# schema_v4_1_SMD_DIP.net
KiCad netlist of a schematic drawn in EAGLE
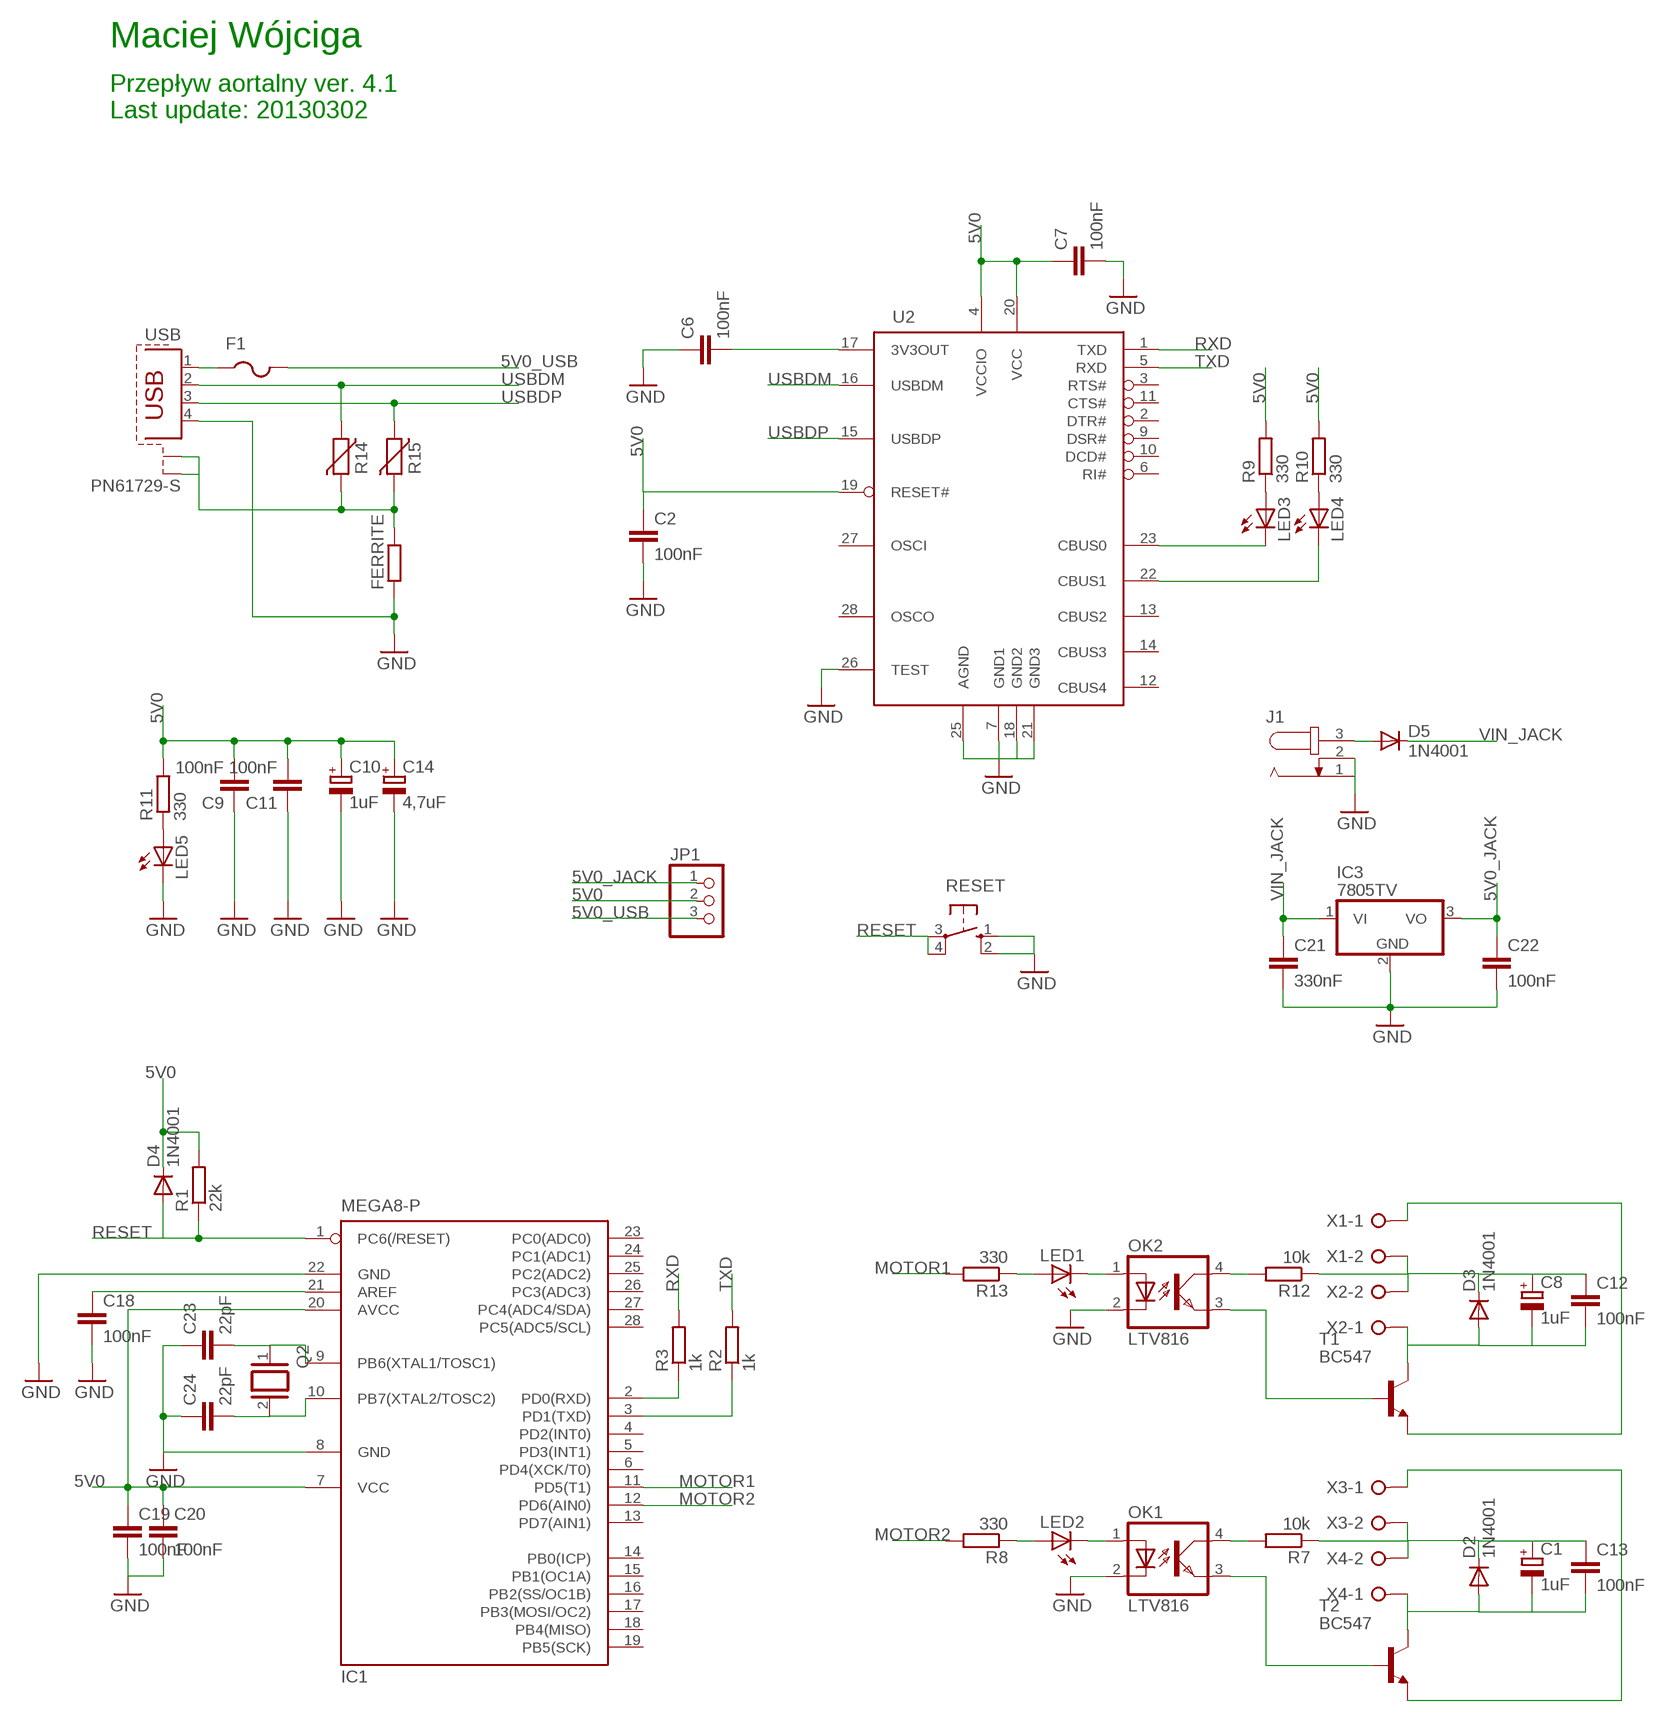
[diagram p0: schematic, sheet 1]

(export (version "E")
  (design (tool "Eeschema 10.0.6"))
  (components
    (comp (ref "C1")
      (value "1uF")
      (footprint "eagle-import:E2,5-5")
      (libsource (lib "eagle-import") (part "CPOL-EUE2.5-5"))
    )
    (comp (ref "C2")
      (value "100nF")
      (footprint "eagle-import:C0603K")
      (libsource (lib "eagle-import") (part "C-EUC0603K"))
    )
    (comp (ref "C6")
      (value "100nF")
      (footprint "eagle-import:C0603K")
      (libsource (lib "eagle-import") (part "C-EUC0603K"))
    )
    (comp (ref "C7")
      (value "100nF")
      (footprint "eagle-import:C0603K")
      (libsource (lib "eagle-import") (part "C-EUC0603K"))
    )
    (comp (ref "C8")
      (value "1uF")
      (footprint "eagle-import:E2,5-5")
      (libsource (lib "eagle-import") (part "CPOL-EUE2.5-5"))
    )
    (comp (ref "C9")
      (value "100nF")
      (footprint "eagle-import:C025-025X050")
      (libsource (lib "eagle-import") (part "C-EU025-025X050"))
    )
    (comp (ref "C10")
      (value "1uF")
      (footprint "eagle-import:E2,5-5")
      (libsource (lib "eagle-import") (part "CPOL-EUE2.5-5"))
    )
    (comp (ref "C11")
      (value "100nF")
      (footprint "eagle-import:C025-025X050")
      (libsource (lib "eagle-import") (part "C-EU025-025X050"))
    )
    (comp (ref "C12")
      (value "100nF")
      (footprint "eagle-import:C025-025X050")
      (libsource (lib "eagle-import") (part "C-EU025-025X050"))
    )
    (comp (ref "C13")
      (value "100nF")
      (footprint "eagle-import:C025-025X050")
      (libsource (lib "eagle-import") (part "C-EU025-025X050"))
    )
    (comp (ref "C14")
      (value "4,7uF")
      (footprint "eagle-import:E2,5-5")
      (libsource (lib "eagle-import") (part "CPOL-EUE2.5-5"))
    )
    (comp (ref "C18")
      (value "100nF")
      (footprint "eagle-import:C0805")
      (libsource (lib "eagle-import") (part "C-EUC0805"))
    )
    (comp (ref "C19")
      (value "100nF")
      (footprint "eagle-import:C025-025X050")
      (libsource (lib "eagle-import") (part "C-EU025-025X050"))
    )
    (comp (ref "C20")
      (value "100nF")
      (footprint "eagle-import:C025-025X050")
      (libsource (lib "eagle-import") (part "C-EU025-025X050"))
    )
    (comp (ref "C21")
      (value "330nF")
      (footprint "eagle-import:C025-025X050")
      (libsource (lib "eagle-import") (part "C-EU025-025X050"))
    )
    (comp (ref "C22")
      (value "100nF")
      (footprint "eagle-import:C025-025X050")
      (libsource (lib "eagle-import") (part "C-EU025-025X050"))
    )
    (comp (ref "C23")
      (value "22pF")
      (footprint "eagle-import:C025-025X050")
      (libsource (lib "eagle-import") (part "C-EU025-025X050"))
    )
    (comp (ref "C24")
      (value "22pF")
      (footprint "eagle-import:C025-025X050")
      (libsource (lib "eagle-import") (part "C-EU025-025X050"))
    )
    (comp (ref "D2")
      (value "1N4001")
      (footprint "eagle-import:DO41-10")
      (libsource (lib "eagle-import") (part "1N4004"))
    )
    (comp (ref "D3")
      (value "1N4001")
      (footprint "eagle-import:DO41-10")
      (libsource (lib "eagle-import") (part "1N4004"))
    )
    (comp (ref "D4")
      (value "1N4001")
      (footprint "eagle-import:DO41-10")
      (libsource (lib "eagle-import") (part "1N4004"))
    )
    (comp (ref "D5")
      (value "1N4001")
      (footprint "eagle-import:DO41-10")
      (libsource (lib "eagle-import") (part "1N4004"))
    )
    (comp (ref "F1")
      (value "PTCFUSE-1812")
      (footprint "eagle-import:1812")
      (libsource (lib "eagle-import") (part "PTCFUSE-1812"))
    )
    (comp (ref "FERRITE")
      (value "R-EU_M0805")
      (footprint "eagle-import:M0805")
      (libsource (lib "eagle-import") (part "resistor_R-EU_M0805"))
    )
    (comp (ref "IC1")
      (value "MEGA8-P")
      (footprint "eagle-import:DIL28-3")
      (libsource (lib "eagle-import") (part "MEGA8-P"))
    )
    (comp (ref "IC3")
      (value "7805TV")
      (footprint "eagle-import:TO220V")
      (libsource (lib "eagle-import") (part "78TV05"))
    )
    (comp (ref "J1")
      (value "JACK-PLUG0")
      (footprint "eagle-import:SPC4077")
      (libsource (lib "eagle-import") (part "JACK-PLUG0"))
    )
    (comp (ref "JP1")
      (value "PINHD-1X3")
      (footprint "eagle-import:1X03")
      (libsource (lib "eagle-import") (part "PINHD-1X3"))
    )
    (comp (ref "LED1")
      (value "LED3MM")
      (footprint "eagle-import:LED3MM")
      (libsource (lib "eagle-import") (part "LED3MM"))
    )
    (comp (ref "LED2")
      (value "LED3MM")
      (footprint "eagle-import:LED3MM")
      (libsource (lib "eagle-import") (part "LED3MM"))
    )
    (comp (ref "LED3")
      (value "LED3MM")
      (footprint "eagle-import:LED3MM")
      (libsource (lib "eagle-import") (part "LED3MM"))
    )
    (comp (ref "LED4")
      (value "LED3MM")
      (footprint "eagle-import:LED3MM")
      (libsource (lib "eagle-import") (part "LED3MM"))
    )
    (comp (ref "LED5")
      (value "LED3MM")
      (footprint "eagle-import:LED3MM")
      (libsource (lib "eagle-import") (part "LED3MM"))
    )
    (comp (ref "OK1")
      (value "LTV816")
      (footprint "eagle-import:DIL04")
      (libsource (lib "eagle-import") (part "LTV816"))
    )
    (comp (ref "OK2")
      (value "LTV816")
      (footprint "eagle-import:DIL04")
      (libsource (lib "eagle-import") (part "LTV816"))
    )
    (comp (ref "Q2")
      (value "XTAL/S")
      (footprint "eagle-import:QS")
      (libsource (lib "eagle-import") (part "XTAL/S"))
    )
    (comp (ref "R1")
      (value "22k")
      (footprint "eagle-import:0207_10")
      (libsource (lib "eagle-import") (part "R-EU_0207/10"))
    )
    (comp (ref "R2")
      (value "1k")
      (footprint "eagle-import:0207_10")
      (libsource (lib "eagle-import") (part "R-EU_0207/10"))
    )
    (comp (ref "R3")
      (value "1k")
      (footprint "eagle-import:0207_10")
      (libsource (lib "eagle-import") (part "R-EU_0207/10"))
    )
    (comp (ref "R7")
      (value "10k")
      (footprint "eagle-import:0207_10")
      (libsource (lib "eagle-import") (part "R-EU_0207/10"))
    )
    (comp (ref "R8")
      (value "330")
      (footprint "eagle-import:0207_10")
      (libsource (lib "eagle-import") (part "R-EU_0207/10"))
    )
    (comp (ref "R9")
      (value "330")
      (footprint "eagle-import:0207_10")
      (libsource (lib "eagle-import") (part "R-EU_0207/10"))
    )
    (comp (ref "R10")
      (value "330")
      (footprint "eagle-import:0207_10")
      (libsource (lib "eagle-import") (part "R-EU_0207/10"))
    )
    (comp (ref "R11")
      (value "330")
      (footprint "eagle-import:0207_10")
      (libsource (lib "eagle-import") (part "R-EU_0207/10"))
    )
    (comp (ref "R12")
      (value "10k")
      (footprint "eagle-import:0207_10")
      (libsource (lib "eagle-import") (part "R-EU_0207/10"))
    )
    (comp (ref "R13")
      (value "330")
      (footprint "eagle-import:0207_10")
      (libsource (lib "eagle-import") (part "R-EU_0207/10"))
    )
    (comp (ref "R14")
      (value "VARISTORCN0603")
      (footprint "eagle-import:CT_CN0603")
      (libsource (lib "eagle-import") (part "VARISTORCN0603"))
    )
    (comp (ref "R15")
      (value "VARISTORCN0603")
      (footprint "eagle-import:CT_CN0603")
      (libsource (lib "eagle-import") (part "VARISTORCN0603"))
    )
    (comp (ref "RESET")
      (value "10-XX")
      (footprint "eagle-import:B3F-10XX")
      (fields (field (name "MPN") "B3F-1000"))
      (libsource (lib "eagle-import") (part "10-XX"))
    )
    (comp (ref "T1")
      (value "BC547")
      (footprint "eagle-import:TO92")
      (libsource (lib "eagle-import") (part "BC547"))
    )
    (comp (ref "T2")
      (value "BC547")
      (footprint "eagle-import:TO92")
      (libsource (lib "eagle-import") (part "BC547"))
    )
    (comp (ref "U2")
      (value "FT232RL")
      (footprint "eagle-import:SSOP28DB")
      (libsource (lib "eagle-import") (part "FT232RL"))
    )
    (comp (ref "USB")
      (value "PN61729-S")
      (footprint "eagle-import:PN61729-S")
      (fields (field (name "OC_FARNELL") "unknown") (field (name "OC_NEWARK") "unknown"))
      (libsource (lib "eagle-import") (part "PN61729-S"))
    )
    (comp (ref "X1")
      (value "W237-02P")
      (footprint "eagle-import:W237-132")
      (fields (field (name "OC_FARNELL") "unknown") (field (name "OC_NEWARK") "unknown"))
      (libsource (lib "eagle-import") (part "W237-02P"))
    )
    (comp (ref "X2")
      (value "W237-02P")
      (footprint "eagle-import:W237-132")
      (fields (field (name "OC_FARNELL") "unknown") (field (name "OC_NEWARK") "unknown"))
      (libsource (lib "eagle-import") (part "W237-02P"))
    )
    (comp (ref "X3")
      (value "W237-02P")
      (footprint "eagle-import:W237-132")
      (fields (field (name "OC_FARNELL") "unknown") (field (name "OC_NEWARK") "unknown"))
      (libsource (lib "eagle-import") (part "W237-02P"))
    )
    (comp (ref "X4")
      (value "W237-02P")
      (footprint "eagle-import:W237-132")
      (fields (field (name "OC_FARNELL") "unknown") (field (name "OC_NEWARK") "unknown"))
      (libsource (lib "eagle-import") (part "W237-02P"))
    )
  )
  (nets
    (net (code "1") (name "/5V0") (class "Default")
      (node (ref "C10") (pin "+") (pinfunction "+_+") (pintype "passive"))
      (node (ref "C11") (pin "2") (pinfunction "2_2") (pintype "passive"))
      (node (ref "C14") (pin "+") (pinfunction "+_+") (pintype "passive"))
      (node (ref "C19") (pin "1") (pinfunction "1_1") (pintype "passive"))
      (node (ref "C2") (pin "1") (pinfunction "1_1") (pintype "passive"))
      (node (ref "C20") (pin "1") (pinfunction "1_1") (pintype "passive"))
      (node (ref "C7") (pin "1") (pinfunction "1_1") (pintype "passive"))
      (node (ref "C9") (pin "2") (pinfunction "2_2") (pintype "passive"))
      (node (ref "D4") (pin "C") (pinfunction "C_C") (pintype "passive"))
      (node (ref "IC1") (pin "20") (pinfunction "AVCC_20") (pintype "power_in"))
      (node (ref "IC1") (pin "7") (pinfunction "VCC_7") (pintype "power_in"))
      (node (ref "JP1") (pin "2") (pinfunction "2_2") (pintype "passive"))
      (node (ref "R1") (pin "2") (pinfunction "2_2") (pintype "passive"))
      (node (ref "R10") (pin "2") (pinfunction "2_2") (pintype "passive"))
      (node (ref "R11") (pin "2") (pinfunction "2_2") (pintype "passive"))
      (node (ref "R9") (pin "2") (pinfunction "2_2") (pintype "passive"))
      (node (ref "U2") (pin "19") (pinfunction "RESET#_19") (pintype "input"))
      (node (ref "U2") (pin "20") (pinfunction "VCC_20") (pintype "power_in"))
      (node (ref "U2") (pin "4") (pinfunction "VCCIO_4") (pintype "power_in"))
    )
    (net (code "2") (name "/5V0_JACK") (class "Default")
      (node (ref "C22") (pin "1") (pinfunction "1_1") (pintype "passive"))
      (node (ref "IC3") (pin "3") (pinfunction "VO_3") (pintype "passive"))
      (node (ref "JP1") (pin "1") (pinfunction "1_1") (pintype "passive"))
    )
    (net (code "3") (name "/5V0_USB") (class "Default")
      (node (ref "F1") (pin "2") (pinfunction "2_2") (pintype "passive"))
      (node (ref "JP1") (pin "3") (pinfunction "3_3") (pintype "passive"))
    )
    (net (code "4") (name "/MOTOR1") (class "Default")
      (node (ref "IC1") (pin "11") (pinfunction "PD5(T1)_11") (pintype "bidirectional"))
      (node (ref "R13") (pin "2") (pinfunction "2_2") (pintype "passive"))
    )
    (net (code "5") (name "/MOTOR2") (class "Default")
      (node (ref "IC1") (pin "12") (pinfunction "PD6(AIN0)_12") (pintype "bidirectional"))
      (node (ref "R8") (pin "2") (pinfunction "2_2") (pintype "passive"))
    )
    (net (code "6") (name "/RESET") (class "Default")
      (node (ref "D4") (pin "A") (pinfunction "A_A") (pintype "passive"))
      (node (ref "IC1") (pin "1") (pinfunction "PC6(/RESET)_1") (pintype "bidirectional"))
      (node (ref "R1") (pin "1") (pinfunction "1_1") (pintype "passive"))
      (node (ref "RESET") (pin "3") (pinfunction "P_3") (pintype "passive"))
      (node (ref "RESET") (pin "4") (pinfunction "P1_4") (pintype "passive"))
    )
    (net (code "7") (name "/RXD") (class "Default")
      (node (ref "R3") (pin "2") (pinfunction "2_2") (pintype "passive"))
      (node (ref "U2") (pin "1") (pinfunction "TXD_1") (pintype "output"))
    )
    (net (code "8") (name "/TXD") (class "Default")
      (node (ref "R2") (pin "2") (pinfunction "2_2") (pintype "passive"))
      (node (ref "U2") (pin "5") (pinfunction "RXD_5") (pintype "input"))
    )
    (net (code "9") (name "/USBDM") (class "Default")
      (node (ref "R14") (pin "1") (pinfunction "1_1") (pintype "passive"))
      (node (ref "U2") (pin "16") (pinfunction "USBDM_16") (pintype "bidirectional"))
      (node (ref "USB") (pin "2") (pinfunction "2_2") (pintype "passive"))
    )
    (net (code "10") (name "/USBDP") (class "Default")
      (node (ref "R15") (pin "1") (pinfunction "1_1") (pintype "passive"))
      (node (ref "U2") (pin "15") (pinfunction "USBDP_15") (pintype "bidirectional"))
      (node (ref "USB") (pin "3") (pinfunction "3_3") (pintype "passive"))
    )
    (net (code "11") (name "/VIN_JACK") (class "Default")
      (node (ref "C21") (pin "1") (pinfunction "1_1") (pintype "passive"))
      (node (ref "D5") (pin "C") (pinfunction "C_C") (pintype "passive"))
      (node (ref "IC3") (pin "1") (pinfunction "VI_1") (pintype "input"))
    )
    (net (code "12") (name "GND") (class "Default")
      (node (ref "C10") (pin "-") (pinfunction "-_-") (pintype "passive"))
      (node (ref "C11") (pin "1") (pinfunction "1_1") (pintype "passive"))
      (node (ref "C14") (pin "-") (pinfunction "-_-") (pintype "passive"))
      (node (ref "C18") (pin "2") (pinfunction "2_2") (pintype "passive"))
      (node (ref "C19") (pin "2") (pinfunction "2_2") (pintype "passive"))
      (node (ref "C2") (pin "2") (pinfunction "2_2") (pintype "passive"))
      (node (ref "C20") (pin "2") (pinfunction "2_2") (pintype "passive"))
      (node (ref "C21") (pin "2") (pinfunction "2_2") (pintype "passive"))
      (node (ref "C22") (pin "2") (pinfunction "2_2") (pintype "passive"))
      (node (ref "C23") (pin "1") (pinfunction "1_1") (pintype "passive"))
      (node (ref "C24") (pin "1") (pinfunction "1_1") (pintype "passive"))
      (node (ref "C6") (pin "1") (pinfunction "1_1") (pintype "passive"))
      (node (ref "C7") (pin "2") (pinfunction "2_2") (pintype "passive"))
      (node (ref "C9") (pin "1") (pinfunction "1_1") (pintype "passive"))
      (node (ref "FERRITE") (pin "1") (pinfunction "1_1") (pintype "passive"))
      (node (ref "IC1") (pin "22") (pinfunction "GND_22") (pintype "power_in"))
      (node (ref "IC1") (pin "8") (pinfunction "GND_8") (pintype "power_in"))
      (node (ref "IC3") (pin "2") (pinfunction "GND_2") (pintype "passive"))
      (node (ref "J1") (pin "1") (pinfunction "1_1") (pintype "passive"))
      (node (ref "J1") (pin "2") (pinfunction "2_2") (pintype "passive"))
      (node (ref "LED5") (pin "K") (pinfunction "C_K") (pintype "passive"))
      (node (ref "OK1") (pin "2") (pinfunction "C_2") (pintype "passive"))
      (node (ref "OK2") (pin "2") (pinfunction "C_2") (pintype "passive"))
      (node (ref "RESET") (pin "1") (pinfunction "S_1") (pintype "passive"))
      (node (ref "RESET") (pin "2") (pinfunction "S1_2") (pintype "passive"))
      (node (ref "U2") (pin "18") (pinfunction "GND2_18") (pintype "power_in"))
      (node (ref "U2") (pin "21") (pinfunction "GND3_21") (pintype "power_in"))
      (node (ref "U2") (pin "25") (pinfunction "AGND_25") (pintype "power_in"))
      (node (ref "U2") (pin "26") (pinfunction "TEST_26") (pintype "input"))
      (node (ref "U2") (pin "7") (pinfunction "GND1_7") (pintype "power_in"))
      (node (ref "USB") (pin "4") (pinfunction "4_4") (pintype "passive"))
    )
    (net (code "13") (name "Net-(D5-PadA)") (class "Default")
      (node (ref "D5") (pin "A") (pinfunction "A_A") (pintype "passive"))
      (node (ref "J1") (pin "3") (pinfunction "3_3") (pintype "passive"))
    )
    (net (code "14") (name "Net-(F1-Pad1)") (class "Default")
      (node (ref "F1") (pin "1") (pinfunction "1_1") (pintype "passive"))
      (node (ref "USB") (pin "1") (pinfunction "1_1") (pintype "passive"))
    )
    (net (code "15") (name "Net-(FERRITE-Pad2)") (class "Default")
      (node (ref "FERRITE") (pin "2") (pinfunction "2_2") (pintype "passive"))
      (node (ref "R14") (pin "2") (pinfunction "2_2") (pintype "passive"))
      (node (ref "R15") (pin "2") (pinfunction "2_2") (pintype "passive"))
      (node (ref "USB") (pin "S1") (pinfunction "S1_S1") (pintype "passive"))
      (node (ref "USB") (pin "S2") (pinfunction "S2_S2") (pintype "passive"))
    )
    (net (code "16") (name "Net-(IC1-AREF)") (class "Default")
      (node (ref "C18") (pin "1") (pinfunction "1_1") (pintype "passive"))
      (node (ref "IC1") (pin "21") (pinfunction "AREF_21") (pintype "passive"))
    )
    (net (code "17") (name "Net-(IC1-PB6(XTAL1{slash}TOSC1))") (class "Default")
      (node (ref "C23") (pin "2") (pinfunction "2_2") (pintype "passive"))
      (node (ref "IC1") (pin "9") (pinfunction "PB6(XTAL1/TOSC1)_9") (pintype "bidirectional"))
      (node (ref "Q2") (pin "1") (pinfunction "1_1") (pintype "passive"))
    )
    (net (code "18") (name "Net-(IC1-PB7(XTAL2{slash}TOSC2))") (class "Default")
      (node (ref "C24") (pin "2") (pinfunction "2_2") (pintype "passive"))
      (node (ref "IC1") (pin "10") (pinfunction "PB7(XTAL2/TOSC2)_10") (pintype "bidirectional"))
      (node (ref "Q2") (pin "2") (pinfunction "2_2") (pintype "passive"))
    )
    (net (code "19") (name "Net-(IC1-PD0(RXD))") (class "Default")
      (node (ref "IC1") (pin "2") (pinfunction "PD0(RXD)_2") (pintype "bidirectional"))
      (node (ref "R3") (pin "1") (pinfunction "1_1") (pintype "passive"))
    )
    (net (code "20") (name "Net-(IC1-PD1(TXD))") (class "Default")
      (node (ref "IC1") (pin "3") (pinfunction "PD1(TXD)_3") (pintype "bidirectional"))
      (node (ref "R2") (pin "1") (pinfunction "1_1") (pintype "passive"))
    )
    (net (code "21") (name "Net-(LED1-C)") (class "Default")
      (node (ref "LED1") (pin "K") (pinfunction "C_K") (pintype "passive"))
      (node (ref "OK2") (pin "1") (pinfunction "A_1") (pintype "passive"))
    )
    (net (code "22") (name "Net-(LED1-PadA)") (class "Default")
      (node (ref "LED1") (pin "A") (pinfunction "A_A") (pintype "passive"))
      (node (ref "R13") (pin "1") (pinfunction "1_1") (pintype "passive"))
    )
    (net (code "23") (name "Net-(LED2-C)") (class "Default")
      (node (ref "LED2") (pin "K") (pinfunction "C_K") (pintype "passive"))
      (node (ref "OK1") (pin "1") (pinfunction "A_1") (pintype "passive"))
    )
    (net (code "24") (name "Net-(LED2-PadA)") (class "Default")
      (node (ref "LED2") (pin "A") (pinfunction "A_A") (pintype "passive"))
      (node (ref "R8") (pin "1") (pinfunction "1_1") (pintype "passive"))
    )
    (net (code "25") (name "Net-(LED3-C)") (class "Default")
      (node (ref "LED3") (pin "K") (pinfunction "C_K") (pintype "passive"))
      (node (ref "U2") (pin "23") (pinfunction "CBUS0_23") (pintype "bidirectional"))
    )
    (net (code "26") (name "Net-(LED3-PadA)") (class "Default")
      (node (ref "LED3") (pin "A") (pinfunction "A_A") (pintype "passive"))
      (node (ref "R9") (pin "1") (pinfunction "1_1") (pintype "passive"))
    )
    (net (code "27") (name "Net-(LED4-C)") (class "Default")
      (node (ref "LED4") (pin "K") (pinfunction "C_K") (pintype "passive"))
      (node (ref "U2") (pin "22") (pinfunction "CBUS1_22") (pintype "bidirectional"))
    )
    (net (code "28") (name "Net-(LED4-PadA)") (class "Default")
      (node (ref "LED4") (pin "A") (pinfunction "A_A") (pintype "passive"))
      (node (ref "R10") (pin "1") (pinfunction "1_1") (pintype "passive"))
    )
    (net (code "29") (name "Net-(LED5-PadA)") (class "Default")
      (node (ref "LED5") (pin "A") (pinfunction "A_A") (pintype "passive"))
      (node (ref "R11") (pin "1") (pinfunction "1_1") (pintype "passive"))
    )
    (net (code "30") (name "Net-(OK1-COL)") (class "Default")
      (node (ref "OK1") (pin "4") (pinfunction "COL_4") (pintype "passive"))
      (node (ref "R7") (pin "2") (pinfunction "2_2") (pintype "passive"))
    )
    (net (code "31") (name "Net-(OK1-EMIT)") (class "Default")
      (node (ref "OK1") (pin "3") (pinfunction "EMIT_3") (pintype "passive"))
      (node (ref "T2") (pin "2") (pinfunction "B_2") (pintype "passive"))
    )
    (net (code "32") (name "Net-(OK2-COL)") (class "Default")
      (node (ref "OK2") (pin "4") (pinfunction "COL_4") (pintype "passive"))
      (node (ref "R12") (pin "2") (pinfunction "2_2") (pintype "passive"))
    )
    (net (code "33") (name "Net-(OK2-EMIT)") (class "Default")
      (node (ref "OK2") (pin "3") (pinfunction "EMIT_3") (pintype "passive"))
      (node (ref "T1") (pin "2") (pinfunction "B_2") (pintype "passive"))
    )
    (net (code "34") (name "Net-(T1-C)") (class "Default")
      (node (ref "C12") (pin "2") (pinfunction "2_2") (pintype "passive"))
      (node (ref "C8") (pin "-") (pinfunction "-_-") (pintype "passive"))
      (node (ref "D3") (pin "A") (pinfunction "A_A") (pintype "passive"))
      (node (ref "T1") (pin "3") (pinfunction "C_3") (pintype "passive"))
      (node (ref "X2") (pin "1") (pinfunction "KL_1") (pintype "passive"))
    )
    (net (code "35") (name "Net-(T1-E)") (class "Default")
      (node (ref "T1") (pin "1") (pinfunction "E_1") (pintype "passive"))
      (node (ref "X1") (pin "1") (pinfunction "KL_1") (pintype "passive"))
    )
    (net (code "36") (name "Net-(T2-C)") (class "Default")
      (node (ref "C1") (pin "-") (pinfunction "-_-") (pintype "passive"))
      (node (ref "C13") (pin "2") (pinfunction "2_2") (pintype "passive"))
      (node (ref "D2") (pin "A") (pinfunction "A_A") (pintype "passive"))
      (node (ref "T2") (pin "3") (pinfunction "C_3") (pintype "passive"))
      (node (ref "X4") (pin "1") (pinfunction "KL_1") (pintype "passive"))
    )
    (net (code "37") (name "Net-(T2-E)") (class "Default")
      (node (ref "T2") (pin "1") (pinfunction "E_1") (pintype "passive"))
      (node (ref "X3") (pin "1") (pinfunction "KL_1") (pintype "passive"))
    )
    (net (code "38") (name "Net-(U2-3V3OUT)") (class "Default")
      (node (ref "C6") (pin "2") (pinfunction "2_2") (pintype "passive"))
      (node (ref "U2") (pin "17") (pinfunction "3V3OUT_17") (pintype "output"))
    )
    (net (code "39") (name "Net-(X1B-KL)") (class "Default")
      (node (ref "C12") (pin "1") (pinfunction "1_1") (pintype "passive"))
      (node (ref "C8") (pin "+") (pinfunction "+_+") (pintype "passive"))
      (node (ref "D3") (pin "C") (pinfunction "C_C") (pintype "passive"))
      (node (ref "R12") (pin "1") (pinfunction "1_1") (pintype "passive"))
      (node (ref "X1") (pin "2") (pinfunction "KL_2") (pintype "passive"))
      (node (ref "X2") (pin "2") (pinfunction "KL_2") (pintype "passive"))
    )
    (net (code "40") (name "Net-(X3B-KL)") (class "Default")
      (node (ref "C1") (pin "+") (pinfunction "+_+") (pintype "passive"))
      (node (ref "C13") (pin "1") (pinfunction "1_1") (pintype "passive"))
      (node (ref "D2") (pin "C") (pinfunction "C_C") (pintype "passive"))
      (node (ref "R7") (pin "1") (pinfunction "1_1") (pintype "passive"))
      (node (ref "X3") (pin "2") (pinfunction "KL_2") (pintype "passive"))
      (node (ref "X4") (pin "2") (pinfunction "KL_2") (pintype "passive"))
    )
    (net (code "41") (name "unconnected-(IC1-PB0(ICP)-Pad14)") (class "Default")
      (node (ref "IC1") (pin "14") (pinfunction "PB0(ICP)_14") (pintype "bidirectional"))
    )
    (net (code "42") (name "unconnected-(IC1-PB1(OC1A)-Pad15)") (class "Default")
      (node (ref "IC1") (pin "15") (pinfunction "PB1(OC1A)_15") (pintype "bidirectional"))
    )
    (net (code "43") (name "unconnected-(IC1-PB2(SS{slash}OC1B)-Pad16)") (class "Default")
      (node (ref "IC1") (pin "16") (pinfunction "PB2(SS/OC1B)_16") (pintype "bidirectional"))
    )
    (net (code "44") (name "unconnected-(IC1-PB3(MOSI{slash}OC2)-Pad17)") (class "Default")
      (node (ref "IC1") (pin "17") (pinfunction "PB3(MOSI/OC2)_17") (pintype "bidirectional"))
    )
    (net (code "45") (name "unconnected-(IC1-PB4(MISO)-Pad18)") (class "Default")
      (node (ref "IC1") (pin "18") (pinfunction "PB4(MISO)_18") (pintype "bidirectional"))
    )
    (net (code "46") (name "unconnected-(IC1-PB5(SCK)-Pad19)") (class "Default")
      (node (ref "IC1") (pin "19") (pinfunction "PB5(SCK)_19") (pintype "bidirectional"))
    )
    (net (code "47") (name "unconnected-(IC1-PC0(ADC0)-Pad23)") (class "Default")
      (node (ref "IC1") (pin "23") (pinfunction "PC0(ADC0)_23") (pintype "bidirectional"))
    )
    (net (code "48") (name "unconnected-(IC1-PC1(ADC1)-Pad24)") (class "Default")
      (node (ref "IC1") (pin "24") (pinfunction "PC1(ADC1)_24") (pintype "bidirectional"))
    )
    (net (code "49") (name "unconnected-(IC1-PC2(ADC2)-Pad25)") (class "Default")
      (node (ref "IC1") (pin "25") (pinfunction "PC2(ADC2)_25") (pintype "bidirectional"))
    )
    (net (code "50") (name "unconnected-(IC1-PC3(ADC3)-Pad26)") (class "Default")
      (node (ref "IC1") (pin "26") (pinfunction "PC3(ADC3)_26") (pintype "bidirectional"))
    )
    (net (code "51") (name "unconnected-(IC1-PC4(ADC4{slash}SDA)-Pad27)") (class "Default")
      (node (ref "IC1") (pin "27") (pinfunction "PC4(ADC4/SDA)_27") (pintype "bidirectional"))
    )
    (net (code "52") (name "unconnected-(IC1-PC5(ADC5{slash}SCL)-Pad28)") (class "Default")
      (node (ref "IC1") (pin "28") (pinfunction "PC5(ADC5/SCL)_28") (pintype "bidirectional"))
    )
    (net (code "53") (name "unconnected-(IC1-PD2(INT0)-Pad4)") (class "Default")
      (node (ref "IC1") (pin "4") (pinfunction "PD2(INT0)_4") (pintype "bidirectional"))
    )
    (net (code "54") (name "unconnected-(IC1-PD3(INT1)-Pad5)") (class "Default")
      (node (ref "IC1") (pin "5") (pinfunction "PD3(INT1)_5") (pintype "bidirectional"))
    )
    (net (code "55") (name "unconnected-(IC1-PD4(XCK{slash}T0)-Pad6)") (class "Default")
      (node (ref "IC1") (pin "6") (pinfunction "PD4(XCK/T0)_6") (pintype "bidirectional"))
    )
    (net (code "56") (name "unconnected-(IC1-PD7(AIN1)-Pad13)") (class "Default")
      (node (ref "IC1") (pin "13") (pinfunction "PD7(AIN1)_13") (pintype "bidirectional"))
    )
    (net (code "57") (name "unconnected-(U2-CBUS2-Pad13)") (class "Default")
      (node (ref "U2") (pin "13") (pinfunction "CBUS2_13") (pintype "bidirectional"))
    )
    (net (code "58") (name "unconnected-(U2-CBUS3-Pad14)") (class "Default")
      (node (ref "U2") (pin "14") (pinfunction "CBUS3_14") (pintype "bidirectional"))
    )
    (net (code "59") (name "unconnected-(U2-CBUS4-Pad12)") (class "Default")
      (node (ref "U2") (pin "12") (pinfunction "CBUS4_12") (pintype "bidirectional"))
    )
    (net (code "60") (name "unconnected-(U2-CTS#-Pad11)") (class "Default")
      (node (ref "U2") (pin "11") (pinfunction "CTS#_11") (pintype "input"))
    )
    (net (code "61") (name "unconnected-(U2-DCD#-Pad10)") (class "Default")
      (node (ref "U2") (pin "10") (pinfunction "DCD#_10") (pintype "input"))
    )
    (net (code "62") (name "unconnected-(U2-DSR#-Pad9)") (class "Default")
      (node (ref "U2") (pin "9") (pinfunction "DSR#_9") (pintype "input"))
    )
    (net (code "63") (name "unconnected-(U2-DTR#-Pad2)") (class "Default")
      (node (ref "U2") (pin "2") (pinfunction "DTR#_2") (pintype "output"))
    )
    (net (code "64") (name "unconnected-(U2-OSCI-Pad27)") (class "Default")
      (node (ref "U2") (pin "27") (pinfunction "OSCI_27") (pintype "input"))
    )
    (net (code "65") (name "unconnected-(U2-OSCO-Pad28)") (class "Default")
      (node (ref "U2") (pin "28") (pinfunction "OSCO_28") (pintype "output"))
    )
    (net (code "66") (name "unconnected-(U2-RI#-Pad6)") (class "Default")
      (node (ref "U2") (pin "6") (pinfunction "RI#_6") (pintype "input"))
    )
    (net (code "67") (name "unconnected-(U2-RTS#-Pad3)") (class "Default")
      (node (ref "U2") (pin "3") (pinfunction "RTS#_3") (pintype "output"))
    )
  )
)
